# 1_WaxWatch.net
KiCad netlist of a schematic drawn in Altium Designer
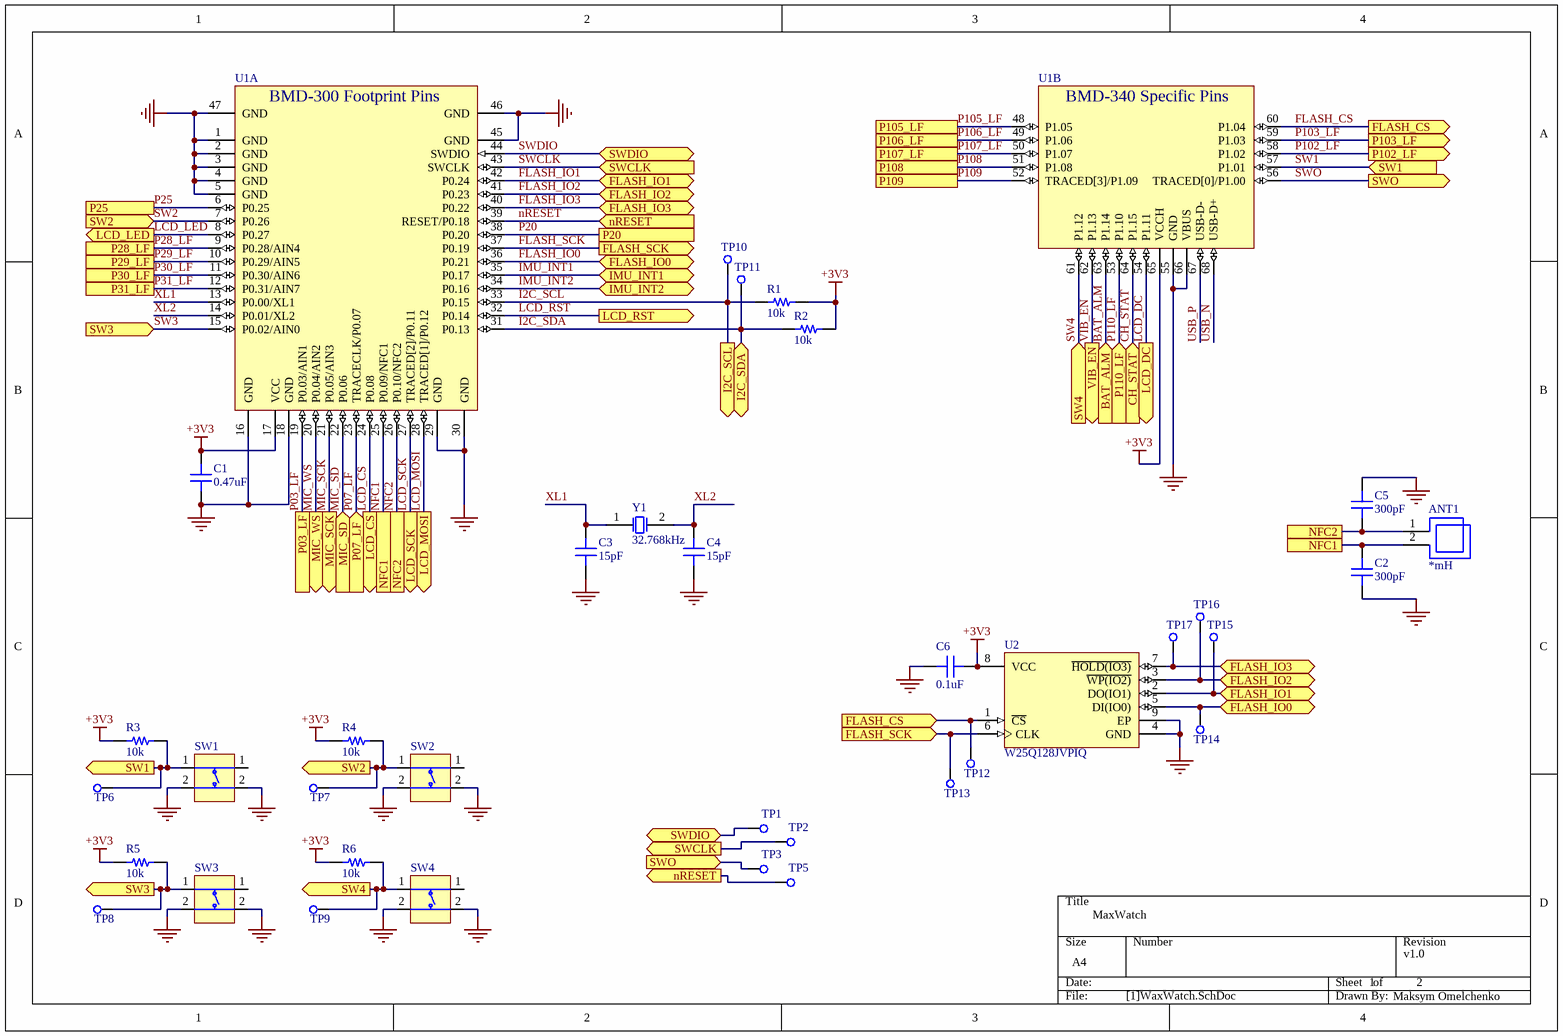
[diagram p0: [1]WaxWatch.SchDoc]

(export (version "E")
  (design (tool "Eeschema 10.0.6"))
  (components
    (comp (ref "ANT1")
      (value "*mH")
      (footprint "PCBComponent_1")
      (fields (field (name "Comment") "NFC_Antenna"))
      (libsource (lib "NFC") (part "NFC_Antenna"))
    )
    (comp (ref "C1")
      (value "0.47uF")
      (footprint "CAP 0402/1005")
      (description "CAP CER 0.47UF 10V X6S 0402")
      (fields
        (field (name "PART NUMBER") "CGB2A1X6S1A474K033BC")
        (field (name "MANUFACTURER") "TDK Corporation")
      )
      (libsource (lib "Celestial Library Database") (part "Capacitor"))
    )
    (comp (ref "C2")
      (value "300pF")
      (footprint "CAP 0402/1005")
      (description "CAP CER 300PF 50V NP0 0402")
      (fields
        (field (name "PART NUMBER") "GRM1555C1H301GA01D")
        (field (name "MANUFACTURER") "Murata Electronics North America")
      )
      (libsource (lib "Celestial Library Database") (part "Capacitor"))
    )
    (comp (ref "C3")
      (value "15pF")
      (footprint "CAP 0402/1005")
      (description "CAP CER 15PF 50V C0G 0402")
      (fields
        (field (name "PART NUMBER") "C1005C0G1H150F050BA")
        (field (name "MANUFACTURER") "TDK Corporation")
      )
      (libsource (lib "Celestial Library Database") (part "Capacitor"))
    )
    (comp (ref "C4")
      (value "15pF")
      (footprint "CAP 0402/1005")
      (description "CAP CER 15PF 50V C0G 0402")
      (fields
        (field (name "PART NUMBER") "C1005C0G1H150F050BA")
        (field (name "MANUFACTURER") "TDK Corporation")
      )
      (libsource (lib "Celestial Library Database") (part "Capacitor"))
    )
    (comp (ref "C5")
      (value "300pF")
      (footprint "CAP 0402/1005")
      (description "CAP CER 300PF 50V NP0 0402")
      (fields
        (field (name "PART NUMBER") "GRM1555C1H301GA01D")
        (field (name "MANUFACTURER") "Murata Electronics North America")
      )
      (libsource (lib "Celestial Library Database") (part "Capacitor"))
    )
    (comp (ref "C6")
      (value "0.1uF")
      (footprint "CAP 0402/1005")
      (description "CAP CER 0.1UF 16V X7R 0402")
      (fields
        (field (name "PART NUMBER") "C1005X7R1C104K050BC")
        (field (name "MANUFACTURER") "TDK Corporation")
      )
      (libsource (lib "Celestial Library Database") (part "Capacitor"))
    )
    (comp (ref "R1")
      (value "10k")
      (footprint "RES 0201/0603")
      (description "RES SMD 10K OHM 5% 1/20W 0201")
      (fields (field (name "PART NUMBER") "RC0201JR-0710KL") (field (name "MANUFACTURER") "Yageo"))
      (libsource (lib "Celestial Library Database") (part "Resistor"))
    )
    (comp (ref "R2")
      (value "10k")
      (footprint "RES 0201/0603")
      (description "RES SMD 10K OHM 5% 1/20W 0201")
      (fields (field (name "PART NUMBER") "RC0201JR-0710KL") (field (name "MANUFACTURER") "Yageo"))
      (libsource (lib "Celestial Library Database") (part "Resistor"))
    )
    (comp (ref "R3")
      (value "10k")
      (footprint "RES 0201/0603")
      (description "RES SMD 10K OHM 5% 1/20W 0201")
      (fields (field (name "PART NUMBER") "RC0201JR-0710KL") (field (name "MANUFACTURER") "Yageo"))
      (libsource (lib "Celestial Library Database") (part "Resistor"))
    )
    (comp (ref "R4")
      (value "10k")
      (footprint "RES 0201/0603")
      (description "RES SMD 10K OHM 5% 1/20W 0201")
      (fields (field (name "PART NUMBER") "RC0201JR-0710KL") (field (name "MANUFACTURER") "Yageo"))
      (libsource (lib "Celestial Library Database") (part "Resistor"))
    )
    (comp (ref "R5")
      (value "10k")
      (footprint "RES 0201/0603")
      (description "RES SMD 10K OHM 5% 1/20W 0201")
      (fields (field (name "PART NUMBER") "RC0201JR-0710KL") (field (name "MANUFACTURER") "Yageo"))
      (libsource (lib "Celestial Library Database") (part "Resistor"))
    )
    (comp (ref "R6")
      (value "10k")
      (footprint "RES 0201/0603")
      (description "RES SMD 10K OHM 5% 1/20W 0201")
      (fields (field (name "PART NUMBER") "RC0201JR-0710KL") (field (name "MANUFACTURER") "Yageo"))
      (libsource (lib "Celestial Library Database") (part "Resistor"))
    )
    (comp (ref "SW1")
      (value "EVQ-P7J01P")
      (footprint "SW_EVQP7J01P")
      (fields (field (name "MF") "Panasonic Electronic"))
      (libsource (lib "EVQ-P7J01P") (part "EVQ-P7J01P"))
    )
    (comp (ref "SW2")
      (value "EVQ-P7J01P")
      (footprint "SW_EVQP7J01P")
      (fields (field (name "MF") "Panasonic Electronic"))
      (libsource (lib "EVQ-P7J01P") (part "EVQ-P7J01P"))
    )
    (comp (ref "SW3")
      (value "EVQ-P7J01P")
      (footprint "SW_EVQP7J01P")
      (fields (field (name "MF") "Panasonic Electronic"))
      (libsource (lib "EVQ-P7J01P") (part "EVQ-P7J01P"))
    )
    (comp (ref "SW4")
      (value "EVQ-P7J01P")
      (footprint "SW_EVQP7J01P")
      (fields (field (name "MF") "Panasonic Electronic"))
      (libsource (lib "EVQ-P7J01P") (part "EVQ-P7J01P"))
    )
    (comp (ref "TP1") (value "TP") (footprint "TP_1.25x1.25") (libsource (lib "TestPoint") (part "TP")))
    (comp (ref "TP2") (value "TP") (footprint "TP_1.25x1.25") (libsource (lib "TestPoint") (part "TP")))
    (comp (ref "TP3") (value "TP") (footprint "TP_1.25x1.25") (libsource (lib "TestPoint") (part "TP")))
    (comp (ref "TP5") (value "TP") (footprint "TP_1.25x1.25") (libsource (lib "TestPoint") (part "TP")))
    (comp (ref "TP6") (value "TP") (footprint "TP_0.75x0.75") (libsource (lib "TestPoint") (part "TP")))
    (comp (ref "TP7") (value "TP") (footprint "TP_0.75x0.75") (libsource (lib "TestPoint") (part "TP")))
    (comp (ref "TP8") (value "TP") (footprint "TP_0.75x0.75") (libsource (lib "TestPoint") (part "TP")))
    (comp (ref "TP9") (value "TP") (footprint "TP_0.75x0.75") (libsource (lib "TestPoint") (part "TP")))
    (comp (ref "TP10") (value "TP") (footprint "TP_0.75x0.75") (libsource (lib "TestPoint") (part "TP")))
    (comp (ref "TP11") (value "TP") (footprint "TP_0.75x0.75") (libsource (lib "TestPoint") (part "TP")))
    (comp (ref "TP12") (value "TP") (footprint "TP_0.75x0.75") (libsource (lib "TestPoint") (part "TP")))
    (comp (ref "TP13") (value "TP") (footprint "TP_0.75x0.75") (libsource (lib "TestPoint") (part "TP")))
    (comp (ref "TP14") (value "TP") (footprint "TP_0.75x0.75") (libsource (lib "TestPoint") (part "TP")))
    (comp (ref "TP15") (value "TP") (footprint "TP_0.75x0.75") (libsource (lib "TestPoint") (part "TP")))
    (comp (ref "TP16") (value "TP") (footprint "TP_0.75x0.75") (libsource (lib "TestPoint") (part "TP")))
    (comp (ref "TP17") (value "TP") (footprint "TP_0.75x0.75") (libsource (lib "TestPoint") (part "TP")))
    (comp (ref "U1")
      (value "BMD-340-A")
      (footprint "BMD-340")
      (description "Bluetooth 5 LE Module, PRELIMINARY, nRF52840, 1MB Flash, 256kB RAM")
      (fields (field (name "MANUFACTURER") "Rigado, Inc") (field (name "MANUFACTURER P/N") "BMD-340-A-ES"))
      (libsource (lib "BMD-340") (part "BMD-340-A"))
    )
    (comp (ref "U2")
      (value "W25Q128JVPIQ")
      (footprint "W25Q128JVPIG")
      (fields (field (name "MANUFACTURER") "Winbond") (field (name "MODEL") "W25Q128JVPIQ"))
      (libsource (lib "W25Q128JVPIQ") (part "W25Q128JVPIQ"))
    )
    (comp (ref "Y1")
      (value "32.768kHz")
      (footprint "KX-327NHT")
      (fields (field (name "PARTNUMBER") "KX-327NHT") (field (name "MANUFACTURER") "GEYER"))
      (libsource (lib "KX-327NHT") (part "KX-327NHT"))
    )
  )
  (nets
    (net (code "1") (name "+3V3") (class "Default")
      (node (ref "C1") (pin "2") (pinfunction "2_2") (pintype "passive"))
      (node (ref "C6") (pin "2") (pinfunction "2_2") (pintype "passive"))
      (node (ref "R1") (pin "1") (pinfunction "1_1") (pintype "passive"))
      (node (ref "R2") (pin "1") (pinfunction "1_1") (pintype "passive"))
      (node (ref "R3") (pin "2") (pinfunction "2_2") (pintype "passive"))
      (node (ref "R4") (pin "2") (pinfunction "2_2") (pintype "passive"))
      (node (ref "R5") (pin "2") (pinfunction "2_2") (pintype "passive"))
      (node (ref "R6") (pin "2") (pinfunction "2_2") (pintype "passive"))
      (node (ref "U1") (pin "17") (pinfunction "VCC_17") (pintype "power_in"))
      (node (ref "U1") (pin "65") (pinfunction "VCCH_65") (pintype "power_in"))
      (node (ref "U2") (pin "8") (pinfunction "VCC_8") (pintype "power_in"))
    )
    (net (code "2") (name "/BAT_ALM") (class "Default")
      (node (ref "U1") (pin "63") (pinfunction "P1.14_63") (pintype "bidirectional"))
    )
    (net (code "3") (name "/CH_STAT") (class "Default")
      (node (ref "U1") (pin "64") (pinfunction "P1.15_64") (pintype "bidirectional"))
    )
    (net (code "4") (name "/FLASH_CS") (class "Default")
      (node (ref "TP12") (pin "1") (pinfunction "TP_1") (pintype "passive"))
      (node (ref "U1") (pin "60") (pinfunction "P1.04_60") (pintype "bidirectional"))
      (node (ref "U2") (pin "1") (pinfunction "~{CS}_1") (pintype "input"))
    )
    (net (code "5") (name "/FLASH_IO0") (class "Default")
      (node (ref "TP14") (pin "1") (pinfunction "TP_1") (pintype "passive"))
      (node (ref "U1") (pin "36") (pinfunction "P0.21_36") (pintype "bidirectional"))
      (node (ref "U2") (pin "5") (pinfunction "DI(IO0)_5") (pintype "bidirectional"))
    )
    (net (code "6") (name "/FLASH_IO1") (class "Default")
      (node (ref "TP15") (pin "1") (pinfunction "TP_1") (pintype "passive"))
      (node (ref "U1") (pin "42") (pinfunction "P0.24_42") (pintype "bidirectional"))
      (node (ref "U2") (pin "2") (pinfunction "DO(IO1)_2") (pintype "bidirectional"))
    )
    (net (code "7") (name "/FLASH_IO2") (class "Default")
      (node (ref "TP16") (pin "1") (pinfunction "TP_1") (pintype "passive"))
      (node (ref "U1") (pin "41") (pinfunction "P0.23_41") (pintype "bidirectional"))
      (node (ref "U2") (pin "3") (pinfunction "~{WP(IO2)}_3") (pintype "bidirectional"))
    )
    (net (code "8") (name "/FLASH_IO3") (class "Default")
      (node (ref "TP17") (pin "1") (pinfunction "TP_1") (pintype "passive"))
      (node (ref "U1") (pin "40") (pinfunction "P0.22_40") (pintype "bidirectional"))
      (node (ref "U2") (pin "7") (pinfunction "~{HOLD(IO3)}_7") (pintype "bidirectional"))
    )
    (net (code "9") (name "/FLASH_SCK") (class "Default")
      (node (ref "TP13") (pin "1") (pinfunction "TP_1") (pintype "passive"))
      (node (ref "U1") (pin "37") (pinfunction "P0.19_37") (pintype "bidirectional"))
      (node (ref "U2") (pin "6") (pinfunction "CLK_6") (pintype "input"))
    )
    (net (code "10") (name "/I2C_SCL") (class "Default")
      (node (ref "R1") (pin "2") (pinfunction "2_2") (pintype "passive"))
      (node (ref "TP10") (pin "1") (pinfunction "TP_1") (pintype "passive"))
      (node (ref "U1") (pin "33") (pinfunction "P0.15_33") (pintype "bidirectional"))
    )
    (net (code "11") (name "/I2C_SDA") (class "Default")
      (node (ref "R2") (pin "2") (pinfunction "2_2") (pintype "passive"))
      (node (ref "TP11") (pin "1") (pinfunction "TP_1") (pintype "passive"))
      (node (ref "U1") (pin "31") (pinfunction "P0.13_31") (pintype "bidirectional"))
    )
    (net (code "12") (name "/IMU_INT1") (class "Default")
      (node (ref "U1") (pin "35") (pinfunction "P0.17_35") (pintype "bidirectional"))
    )
    (net (code "13") (name "/IMU_INT2") (class "Default")
      (node (ref "U1") (pin "34") (pinfunction "P0.16_34") (pintype "bidirectional"))
    )
    (net (code "14") (name "/LCD_CS") (class "Default")
      (node (ref "U1") (pin "24") (pinfunction "P0.08_24") (pintype "bidirectional"))
    )
    (net (code "15") (name "/LCD_DC") (class "Default")
      (node (ref "U1") (pin "54") (pinfunction "P1.11_54") (pintype "bidirectional"))
    )
    (net (code "16") (name "/LCD_LED") (class "Default")
      (node (ref "U1") (pin "8") (pinfunction "P0.27_8") (pintype "bidirectional"))
    )
    (net (code "17") (name "/LCD_MOSI") (class "Default")
      (node (ref "U1") (pin "28") (pinfunction "TRACED[1]/P0.12_28") (pintype "bidirectional"))
    )
    (net (code "18") (name "/LCD_RST") (class "Default")
      (node (ref "U1") (pin "32") (pinfunction "P0.14_32") (pintype "bidirectional"))
    )
    (net (code "19") (name "/LCD_SCK") (class "Default")
      (node (ref "U1") (pin "27") (pinfunction "TRACED[2]/P0.11_27") (pintype "bidirectional"))
    )
    (net (code "20") (name "/MIC_SCK") (class "Default")
      (node (ref "U1") (pin "21") (pinfunction "P0.05/AIN3_21") (pintype "bidirectional"))
    )
    (net (code "21") (name "/MIC_SD") (class "Default")
      (node (ref "U1") (pin "22") (pinfunction "P0.06_22") (pintype "bidirectional"))
    )
    (net (code "22") (name "/MIC_WS") (class "Default")
      (node (ref "U1") (pin "20") (pinfunction "P0.04/AIN2_20") (pintype "bidirectional"))
    )
    (net (code "23") (name "/NFC1") (class "Default")
      (node (ref "ANT1") (pin "2") (pintype "passive"))
      (node (ref "C2") (pin "2") (pinfunction "2_2") (pintype "passive"))
      (node (ref "U1") (pin "25") (pinfunction "P0.09/NFC1_25") (pintype "bidirectional"))
    )
    (net (code "24") (name "/NFC2") (class "Default")
      (node (ref "ANT1") (pin "1") (pintype "passive"))
      (node (ref "C5") (pin "1") (pinfunction "1_1") (pintype "passive"))
      (node (ref "U1") (pin "26") (pinfunction "P0.10/NFC2_26") (pintype "bidirectional"))
    )
    (net (code "25") (name "/P03_LF") (class "Default")
      (node (ref "U1") (pin "19") (pinfunction "P0.03/AIN1_19") (pintype "bidirectional"))
    )
    (net (code "26") (name "/P07_LF") (class "Default")
      (node (ref "U1") (pin "23") (pinfunction "TRACECLK/P0.07_23") (pintype "bidirectional"))
    )
    (net (code "27") (name "/P20") (class "Default")
      (node (ref "U1") (pin "38") (pinfunction "P0.20_38") (pintype "bidirectional"))
    )
    (net (code "28") (name "/P25") (class "Default")
      (node (ref "U1") (pin "6") (pinfunction "P0.25_6") (pintype "bidirectional"))
    )
    (net (code "29") (name "/P28_LF") (class "Default")
      (node (ref "U1") (pin "9") (pinfunction "P0.28/AIN4_9") (pintype "bidirectional"))
    )
    (net (code "30") (name "/P29_LF") (class "Default")
      (node (ref "U1") (pin "10") (pinfunction "P0.29/AIN5_10") (pintype "bidirectional"))
    )
    (net (code "31") (name "/P30_LF") (class "Default")
      (node (ref "U1") (pin "11") (pinfunction "P0.30/AIN6_11") (pintype "bidirectional"))
    )
    (net (code "32") (name "/P31_LF") (class "Default")
      (node (ref "U1") (pin "12") (pinfunction "P0.31/AIN7_12") (pintype "bidirectional"))
    )
    (net (code "33") (name "/P102_LF") (class "Default")
      (node (ref "U1") (pin "58") (pinfunction "P1.02_58") (pintype "bidirectional"))
    )
    (net (code "34") (name "/P103_LF") (class "Default")
      (node (ref "U1") (pin "59") (pinfunction "P1.03_59") (pintype "bidirectional"))
    )
    (net (code "35") (name "/P105_LF") (class "Default")
      (node (ref "U1") (pin "48") (pinfunction "P1.05_48") (pintype "bidirectional"))
    )
    (net (code "36") (name "/P106_LF") (class "Default")
      (node (ref "U1") (pin "49") (pinfunction "P1.06_49") (pintype "bidirectional"))
    )
    (net (code "37") (name "/P107_LF") (class "Default")
      (node (ref "U1") (pin "50") (pinfunction "P1.07_50") (pintype "bidirectional"))
    )
    (net (code "38") (name "/P108") (class "Default")
      (node (ref "U1") (pin "51") (pinfunction "P1.08_51") (pintype "bidirectional"))
    )
    (net (code "39") (name "/P109") (class "Default")
      (node (ref "U1") (pin "52") (pinfunction "TRACED[3]/P1.09_52") (pintype "bidirectional"))
    )
    (net (code "40") (name "/P110_LF") (class "Default")
      (node (ref "U1") (pin "53") (pinfunction "P1.10_53") (pintype "bidirectional"))
    )
    (net (code "41") (name "/SW1") (class "Default")
      (node (ref "R3") (pin "1") (pinfunction "1_1") (pintype "passive"))
      (node (ref "SW1") (pin "1") (pintype "passive"))
      (node (ref "TP6") (pin "1") (pinfunction "TP_1") (pintype "passive"))
      (node (ref "U1") (pin "57") (pinfunction "P1.01_57") (pintype "bidirectional"))
    )
    (net (code "42") (name "/SW2") (class "Default")
      (node (ref "R4") (pin "1") (pinfunction "1_1") (pintype "passive"))
      (node (ref "SW2") (pin "1") (pintype "passive"))
      (node (ref "TP7") (pin "1") (pinfunction "TP_1") (pintype "passive"))
      (node (ref "U1") (pin "7") (pinfunction "P0.26_7") (pintype "bidirectional"))
    )
    (net (code "43") (name "/SW3") (class "Default")
      (node (ref "R5") (pin "1") (pinfunction "1_1") (pintype "passive"))
      (node (ref "SW3") (pin "1") (pintype "passive"))
      (node (ref "TP8") (pin "1") (pinfunction "TP_1") (pintype "passive"))
      (node (ref "U1") (pin "15") (pinfunction "P0.02/AIN0_15") (pintype "bidirectional"))
    )
    (net (code "44") (name "/SW4") (class "Default")
      (node (ref "R6") (pin "1") (pinfunction "1_1") (pintype "passive"))
      (node (ref "SW4") (pin "1") (pintype "passive"))
      (node (ref "TP9") (pin "1") (pinfunction "TP_1") (pintype "passive"))
      (node (ref "U1") (pin "61") (pinfunction "P1.12_61") (pintype "bidirectional"))
    )
    (net (code "45") (name "/SWCLK") (class "Default")
      (node (ref "TP2") (pin "1") (pinfunction "TP_1") (pintype "passive"))
      (node (ref "U1") (pin "43") (pinfunction "SWCLK_43") (pintype "bidirectional"))
    )
    (net (code "46") (name "/SWDIO") (class "Default")
      (node (ref "TP1") (pin "1") (pinfunction "TP_1") (pintype "passive"))
      (node (ref "U1") (pin "44") (pinfunction "SWDIO_44") (pintype "input"))
    )
    (net (code "47") (name "/SWO") (class "Default")
      (node (ref "TP3") (pin "1") (pinfunction "TP_1") (pintype "passive"))
      (node (ref "U1") (pin "56") (pinfunction "TRACED[0]/P1.00_56") (pintype "bidirectional"))
    )
    (net (code "48") (name "/USB_N") (class "Default")
      (node (ref "U1") (pin "68") (pinfunction "USB-D+_68") (pintype "bidirectional"))
    )
    (net (code "49") (name "/USB_P") (class "Default")
      (node (ref "U1") (pin "67") (pinfunction "USB-D-_67") (pintype "bidirectional"))
    )
    (net (code "50") (name "/VIB_EN") (class "Default")
      (node (ref "U1") (pin "62") (pinfunction "P1.13_62") (pintype "bidirectional"))
    )
    (net (code "51") (name "/XL1") (class "Default")
      (node (ref "C3") (pin "2") (pinfunction "2_2") (pintype "passive"))
      (node (ref "U1") (pin "13") (pinfunction "P0.00/XL1_13") (pintype "bidirectional"))
      (node (ref "Y1") (pin "1") (pinfunction "X1_1") (pintype "passive"))
    )
    (net (code "52") (name "/XL2") (class "Default")
      (node (ref "C4") (pin "2") (pinfunction "2_2") (pintype "passive"))
      (node (ref "U1") (pin "14") (pinfunction "P0.01/XL2_14") (pintype "bidirectional"))
      (node (ref "Y1") (pin "2") (pinfunction "X2_2") (pintype "passive"))
    )
    (net (code "53") (name "/nRESET") (class "Default")
      (node (ref "TP5") (pin "1") (pinfunction "TP_1") (pintype "passive"))
      (node (ref "U1") (pin "39") (pinfunction "RESET/P0.18_39") (pintype "bidirectional"))
    )
    (net (code "54") (name "GND") (class "Default")
      (node (ref "C1") (pin "1") (pinfunction "1_1") (pintype "passive"))
      (node (ref "C2") (pin "1") (pinfunction "1_1") (pintype "passive"))
      (node (ref "C3") (pin "1") (pinfunction "1_1") (pintype "passive"))
      (node (ref "C4") (pin "1") (pinfunction "1_1") (pintype "passive"))
      (node (ref "C5") (pin "2") (pinfunction "2_2") (pintype "passive"))
      (node (ref "C6") (pin "1") (pinfunction "1_1") (pintype "passive"))
      (node (ref "SW1") (pin "2") (pintype "passive"))
      (node (ref "SW2") (pin "2") (pintype "passive"))
      (node (ref "SW3") (pin "2") (pintype "passive"))
      (node (ref "SW4") (pin "2") (pintype "passive"))
      (node (ref "U1") (pin "1") (pinfunction "GND_1") (pintype "power_in"))
      (node (ref "U1") (pin "16") (pinfunction "GND_16") (pintype "power_in"))
      (node (ref "U1") (pin "18") (pinfunction "GND_18") (pintype "power_in"))
      (node (ref "U1") (pin "2") (pinfunction "GND_2") (pintype "power_in"))
      (node (ref "U1") (pin "29") (pinfunction "GND_29") (pintype "power_in"))
      (node (ref "U1") (pin "3") (pinfunction "GND_3") (pintype "power_in"))
      (node (ref "U1") (pin "30") (pinfunction "GND_30") (pintype "power_in"))
      (node (ref "U1") (pin "4") (pinfunction "GND_4") (pintype "power_in"))
      (node (ref "U1") (pin "45") (pinfunction "GND_45") (pintype "power_in"))
      (node (ref "U1") (pin "46") (pinfunction "GND_46") (pintype "power_in"))
      (node (ref "U1") (pin "47") (pinfunction "GND_47") (pintype "power_in"))
      (node (ref "U1") (pin "5") (pinfunction "GND_5") (pintype "power_in"))
      (node (ref "U1") (pin "55") (pinfunction "GND_55") (pintype "power_in"))
      (node (ref "U1") (pin "66") (pinfunction "VBUS_66") (pintype "power_in"))
      (node (ref "U2") (pin "4") (pinfunction "GND_4") (pintype "power_in"))
      (node (ref "U2") (pin "9") (pinfunction "EP_9") (pintype "passive"))
    )
    (net (code "55") (name "unconnected-(SW1-Pad1)") (class "Default")
      (node (ref "SW1") (pin "1") (pintype "passive"))
    )
    (net (code "56") (name "unconnected-(SW2-Pad1)") (class "Default")
      (node (ref "SW2") (pin "1") (pintype "passive"))
    )
    (net (code "57") (name "unconnected-(SW3-Pad1)") (class "Default")
      (node (ref "SW3") (pin "1") (pintype "passive"))
    )
    (net (code "58") (name "unconnected-(SW4-Pad1)") (class "Default")
      (node (ref "SW4") (pin "1") (pintype "passive"))
    )
  )
)
